# LPCB278_-_RELAYS.net
KiCad netlist of a schematic drawn in Altium Designer
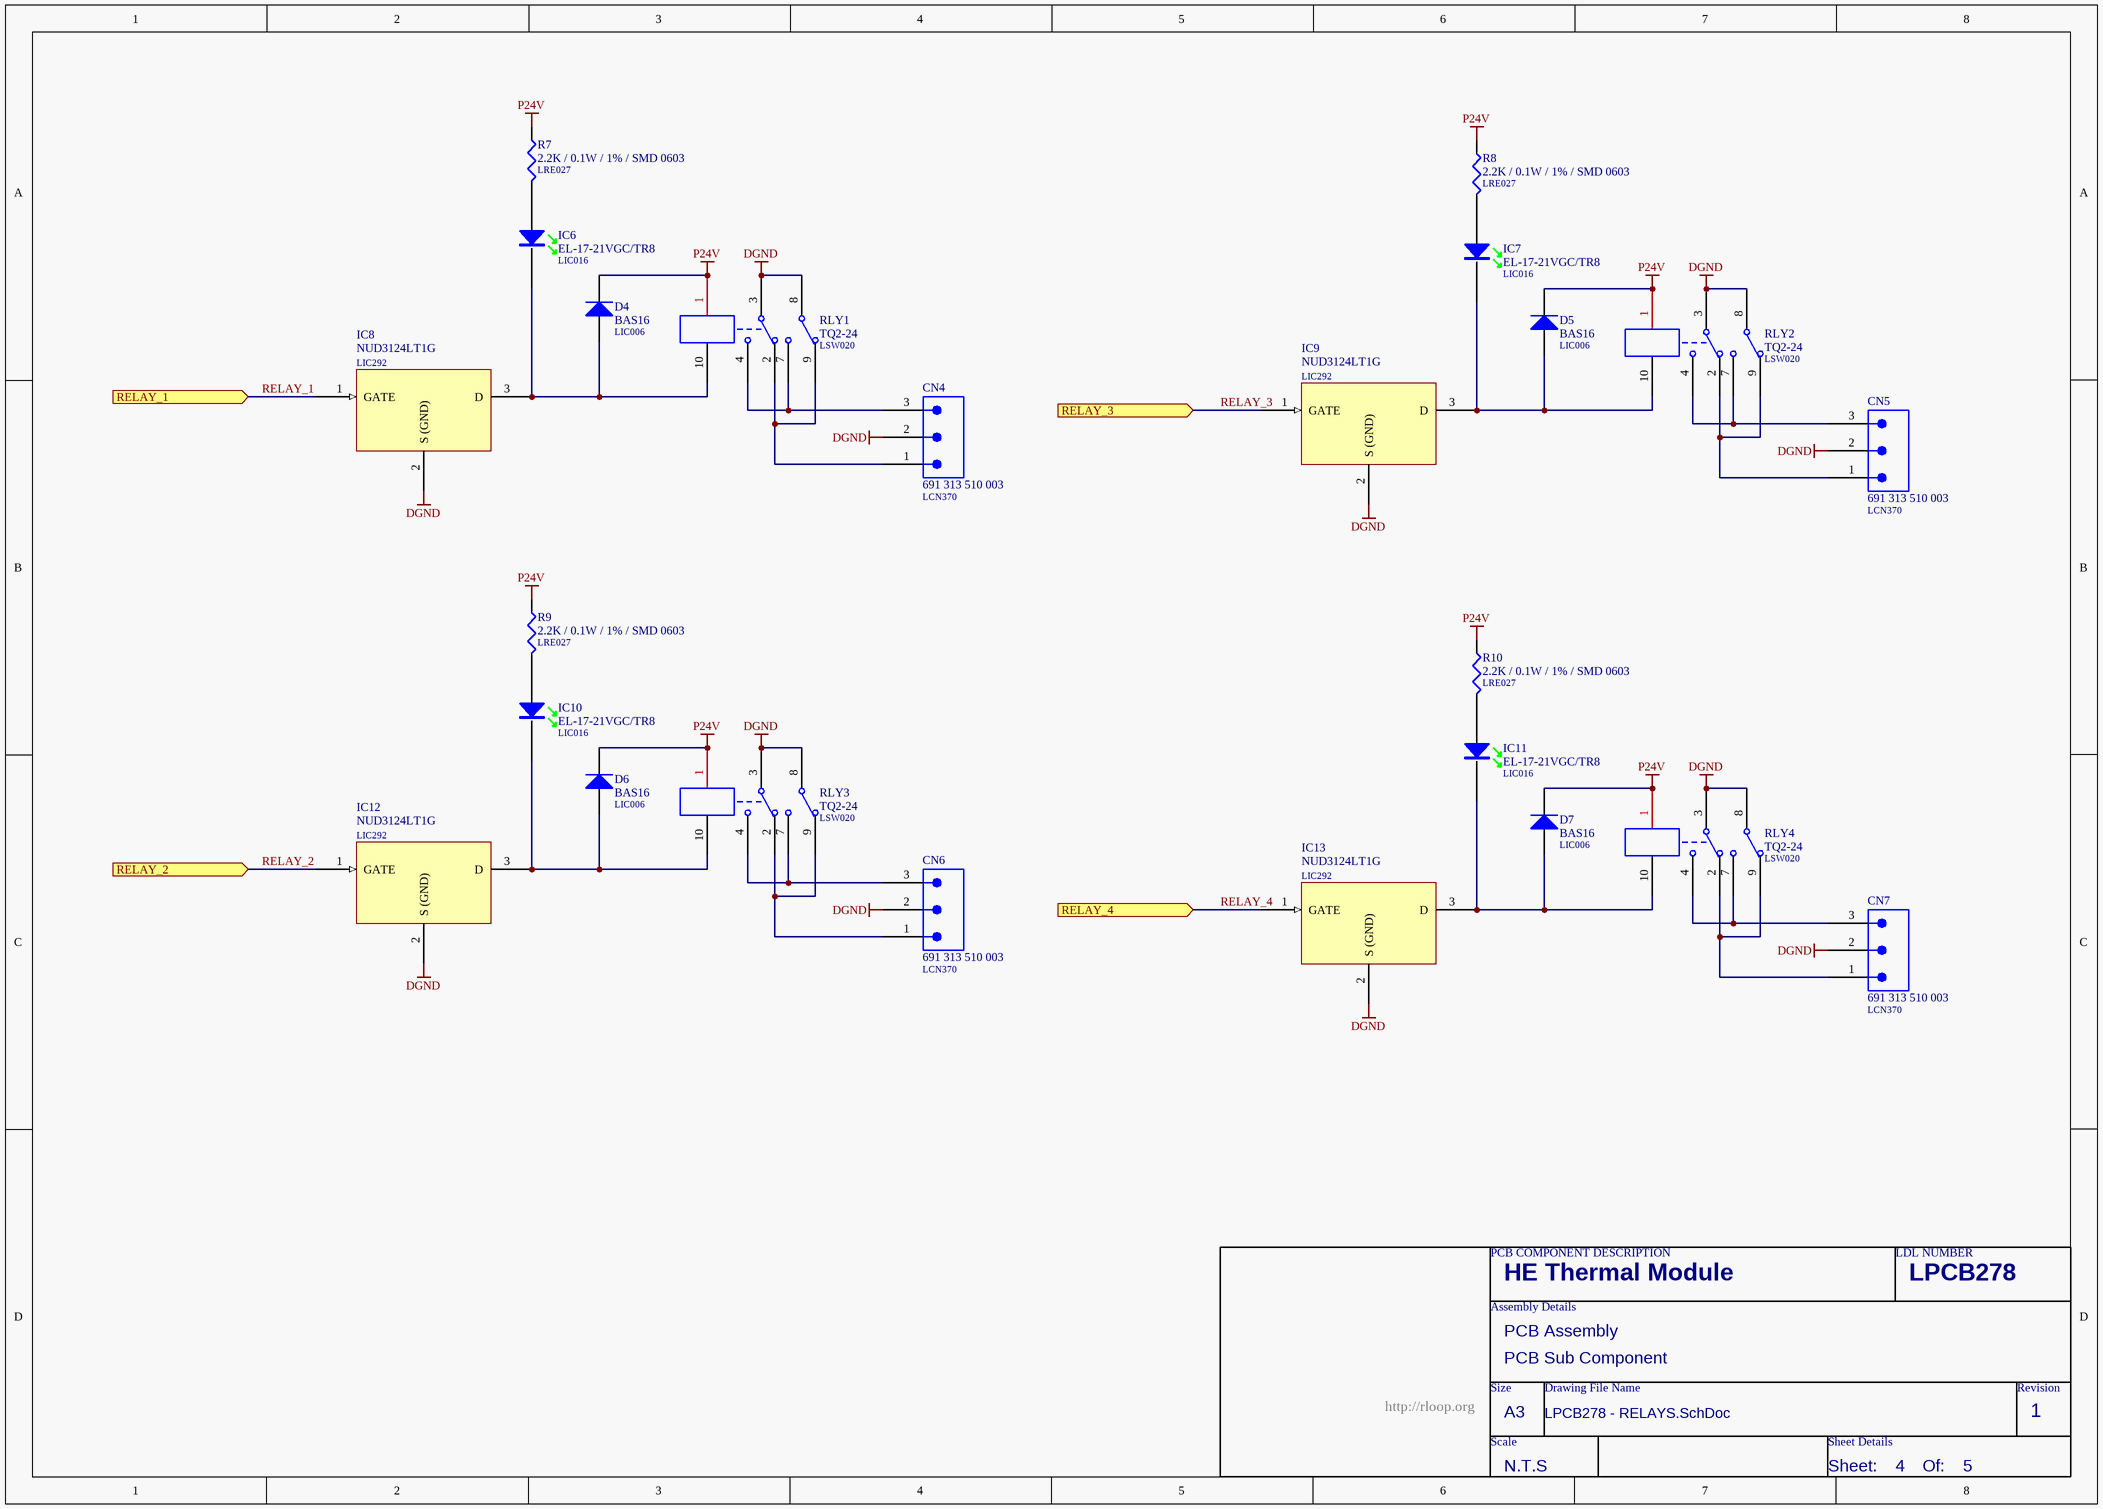
[diagram p0: LPCB278 - RELAYS.SchDoc]

(export (version "E")
  (design (tool "Eeschema 10.0.6"))
  (components
    (comp (ref "CN4")
      (value "691 313 510 003")
      (footprint "691 313 510 003")
      (description "Connector, Pluggable Terminal Block, 5.08mm, 3 Way, PTH")
      (fields (field (name "LDL_NUMBER") "LCN370"))
      (libsource (lib "LDL_Connectors") (part "691 313 510 003"))
    )
    (comp (ref "CN5")
      (value "691 313 510 003")
      (footprint "691 313 510 003")
      (description "Connector, Pluggable Terminal Block, 5.08mm, 3 Way, PTH")
      (fields (field (name "LDL_NUMBER") "LCN370"))
      (libsource (lib "LDL_Connectors") (part "691 313 510 003"))
    )
    (comp (ref "CN6")
      (value "691 313 510 003")
      (footprint "691 313 510 003")
      (description "Connector, Pluggable Terminal Block, 5.08mm, 3 Way, PTH")
      (fields (field (name "LDL_NUMBER") "LCN370"))
      (libsource (lib "LDL_Connectors") (part "691 313 510 003"))
    )
    (comp (ref "CN7")
      (value "691 313 510 003")
      (footprint "691 313 510 003")
      (description "Connector, Pluggable Terminal Block, 5.08mm, 3 Way, PTH")
      (fields (field (name "LDL_NUMBER") "LCN370"))
      (libsource (lib "LDL_Connectors") (part "691 313 510 003"))
    )
    (comp (ref "D4")
      (value "BAS16")
      (footprint "LFP021__SOT23")
      (description "Diode, Small Signal, 0.2A, 85V, SMD SOT-23 [LIC006]")
      (fields (field (name "LDL_NUMBER") "LIC006"))
      (libsource (lib "LDL_Semiconductors") (part "BAS16"))
    )
    (comp (ref "D5")
      (value "BAS16")
      (footprint "LFP021__SOT23")
      (description "Diode, Small Signal, 0.2A, 85V, SMD SOT-23 [LIC006]")
      (fields (field (name "LDL_NUMBER") "LIC006"))
      (libsource (lib "LDL_Semiconductors") (part "BAS16"))
    )
    (comp (ref "D6")
      (value "BAS16")
      (footprint "LFP021__SOT23")
      (description "Diode, Small Signal, 0.2A, 85V, SMD SOT-23 [LIC006]")
      (fields (field (name "LDL_NUMBER") "LIC006"))
      (libsource (lib "LDL_Semiconductors") (part "BAS16"))
    )
    (comp (ref "D7")
      (value "BAS16")
      (footprint "LFP021__SOT23")
      (description "Diode, Small Signal, 0.2A, 85V, SMD SOT-23 [LIC006]")
      (fields (field (name "LDL_NUMBER") "LIC006"))
      (libsource (lib "LDL_Semiconductors") (part "BAS16"))
    )
    (comp (ref "IC6")
      (value "EL-17-21VGC/TR8")
      (footprint "CR2012-0805-LED")
      (description "LED, SMD, 0805 Green [LIC016]")
      (fields (field (name "LDL_NUMBER") "LIC016"))
      (libsource (lib "LDL_Semiconductors") (part "EL-17-21VGC/TR8"))
    )
    (comp (ref "IC7")
      (value "EL-17-21VGC/TR8")
      (footprint "CR2012-0805-LED")
      (description "LED, SMD, 0805 Green [LIC016]")
      (fields (field (name "LDL_NUMBER") "LIC016"))
      (libsource (lib "LDL_Semiconductors") (part "EL-17-21VGC/TR8"))
    )
    (comp (ref "IC8")
      (value "NUD3124LT1G")
      (footprint "LFP021__SOT23")
      (description "IC, Relay Driver, 28V Industrial, SMD SOT23 [LIC292]")
      (fields (field (name "LDL_NUMBER") "LIC292"))
      (libsource (lib "LDL_Semiconductors") (part "NUD3124LT1G"))
    )
    (comp (ref "IC9")
      (value "NUD3124LT1G")
      (footprint "LFP021__SOT23")
      (description "IC, Relay Driver, 28V Industrial, SMD SOT23 [LIC292]")
      (fields (field (name "LDL_NUMBER") "LIC292"))
      (libsource (lib "LDL_Semiconductors") (part "NUD3124LT1G"))
    )
    (comp (ref "IC10")
      (value "EL-17-21VGC/TR8")
      (footprint "CR2012-0805-LED")
      (description "LED, SMD, 0805 Green [LIC016]")
      (fields (field (name "LDL_NUMBER") "LIC016"))
      (libsource (lib "LDL_Semiconductors") (part "EL-17-21VGC/TR8"))
    )
    (comp (ref "IC11")
      (value "EL-17-21VGC/TR8")
      (footprint "CR2012-0805-LED")
      (description "LED, SMD, 0805 Green [LIC016]")
      (fields (field (name "LDL_NUMBER") "LIC016"))
      (libsource (lib "LDL_Semiconductors") (part "EL-17-21VGC/TR8"))
    )
    (comp (ref "IC12")
      (value "NUD3124LT1G")
      (footprint "LFP021__SOT23")
      (description "IC, Relay Driver, 28V Industrial, SMD SOT23 [LIC292]")
      (fields (field (name "LDL_NUMBER") "LIC292"))
      (libsource (lib "LDL_Semiconductors") (part "NUD3124LT1G"))
    )
    (comp (ref "IC13")
      (value "NUD3124LT1G")
      (footprint "LFP021__SOT23")
      (description "IC, Relay Driver, 28V Industrial, SMD SOT23 [LIC292]")
      (fields (field (name "LDL_NUMBER") "LIC292"))
      (libsource (lib "LDL_Semiconductors") (part "NUD3124LT1G"))
    )
    (comp (ref "R7")
      (value "2.2K / 0.1W / 1% / SMD 0603")
      (footprint "LFP020__CR1608-0603-IPC7351_B")
      (description "Resistor, Ceramic Chip, 2.2K, 0.1W, 1%, SMD 0603 [LRE027]")
      (fields (field (name "LDL_NUMBER") "LRE027"))
      (libsource (lib "LDL_Resistors") (part "2.2K / 0.1W / 1% / SMD 0603"))
    )
    (comp (ref "R8")
      (value "2.2K / 0.1W / 1% / SMD 0603")
      (footprint "LFP020__CR1608-0603-IPC7351_B")
      (description "Resistor, Ceramic Chip, 2.2K, 0.1W, 1%, SMD 0603 [LRE027]")
      (fields (field (name "LDL_NUMBER") "LRE027"))
      (libsource (lib "LDL_Resistors") (part "2.2K / 0.1W / 1% / SMD 0603"))
    )
    (comp (ref "R9")
      (value "2.2K / 0.1W / 1% / SMD 0603")
      (footprint "LFP020__CR1608-0603-IPC7351_B")
      (description "Resistor, Ceramic Chip, 2.2K, 0.1W, 1%, SMD 0603 [LRE027]")
      (fields (field (name "LDL_NUMBER") "LRE027"))
      (libsource (lib "LDL_Resistors") (part "2.2K / 0.1W / 1% / SMD 0603"))
    )
    (comp (ref "R10")
      (value "2.2K / 0.1W / 1% / SMD 0603")
      (footprint "LFP020__CR1608-0603-IPC7351_B")
      (description "Resistor, Ceramic Chip, 2.2K, 0.1W, 1%, SMD 0603 [LRE027]")
      (fields (field (name "LDL_NUMBER") "LRE027"))
      (libsource (lib "LDL_Resistors") (part "2.2K / 0.1W / 1% / SMD 0603"))
    )
    (comp (ref "RLY1")
      (value "TQ2-24")
      (footprint "TQ2")
      (description "Relay, DPDT, Non Latching, 24VDC Coil, 1A Rating, PTH")
      (fields (field (name "LDL_NUMBER") "LSW020"))
      (libsource (lib "LDL_Switching") (part "TQ2-24"))
    )
    (comp (ref "RLY2")
      (value "TQ2-24")
      (footprint "TQ2")
      (description "Relay, DPDT, Non Latching, 24VDC Coil, 1A Rating, PTH")
      (fields (field (name "LDL_NUMBER") "LSW020"))
      (libsource (lib "LDL_Switching") (part "TQ2-24"))
    )
    (comp (ref "RLY3")
      (value "TQ2-24")
      (footprint "TQ2")
      (description "Relay, DPDT, Non Latching, 24VDC Coil, 1A Rating, PTH")
      (fields (field (name "LDL_NUMBER") "LSW020"))
      (libsource (lib "LDL_Switching") (part "TQ2-24"))
    )
    (comp (ref "RLY4")
      (value "TQ2-24")
      (footprint "TQ2")
      (description "Relay, DPDT, Non Latching, 24VDC Coil, 1A Rating, PTH")
      (fields (field (name "LDL_NUMBER") "LSW020"))
      (libsource (lib "LDL_Switching") (part "TQ2-24"))
    )
  )
  (nets
    (net (code "1") (name "/RELAY_1") (class "Default")
      (node (ref "IC8") (pin "1") (pinfunction "GATE_1") (pintype "input"))
    )
    (net (code "2") (name "/RELAY_2") (class "Default")
      (node (ref "IC12") (pin "1") (pinfunction "GATE_1") (pintype "input"))
    )
    (net (code "3") (name "/RELAY_3") (class "Default")
      (node (ref "IC9") (pin "1") (pinfunction "GATE_1") (pintype "input"))
    )
    (net (code "4") (name "/RELAY_4") (class "Default")
      (node (ref "IC13") (pin "1") (pinfunction "GATE_1") (pintype "input"))
    )
    (net (code "5") (name "DGND") (class "Default")
      (node (ref "CN4") (pin "2") (pinfunction "2_2") (pintype "passive"))
      (node (ref "CN5") (pin "2") (pinfunction "2_2") (pintype "passive"))
      (node (ref "CN6") (pin "2") (pinfunction "2_2") (pintype "passive"))
      (node (ref "CN7") (pin "2") (pinfunction "2_2") (pintype "passive"))
      (node (ref "IC12") (pin "2") (pinfunction "S_(GND)_2") (pintype "passive"))
      (node (ref "IC13") (pin "2") (pinfunction "S_(GND)_2") (pintype "passive"))
      (node (ref "IC8") (pin "2") (pinfunction "S_(GND)_2") (pintype "passive"))
      (node (ref "IC9") (pin "2") (pinfunction "S_(GND)_2") (pintype "passive"))
      (node (ref "RLY1") (pin "3") (pinfunction "3_3") (pintype "passive"))
      (node (ref "RLY1") (pin "8") (pinfunction "8_8") (pintype "passive"))
      (node (ref "RLY2") (pin "3") (pinfunction "3_3") (pintype "passive"))
      (node (ref "RLY2") (pin "8") (pinfunction "8_8") (pintype "passive"))
      (node (ref "RLY3") (pin "3") (pinfunction "3_3") (pintype "passive"))
      (node (ref "RLY3") (pin "8") (pinfunction "8_8") (pintype "passive"))
      (node (ref "RLY4") (pin "3") (pinfunction "3_3") (pintype "passive"))
      (node (ref "RLY4") (pin "8") (pinfunction "8_8") (pintype "passive"))
    )
    (net (code "6") (name "Net-(CN4-Pad1)") (class "Default")
      (node (ref "CN4") (pin "1") (pinfunction "1_1") (pintype "passive"))
      (node (ref "RLY1") (pin "2") (pinfunction "2_2") (pintype "passive"))
      (node (ref "RLY1") (pin "9") (pinfunction "9_9") (pintype "passive"))
    )
    (net (code "7") (name "Net-(CN4-Pad3)") (class "Default")
      (node (ref "CN4") (pin "3") (pinfunction "3_3") (pintype "passive"))
      (node (ref "RLY1") (pin "4") (pinfunction "4_4") (pintype "passive"))
      (node (ref "RLY1") (pin "7") (pinfunction "7_7") (pintype "passive"))
    )
    (net (code "8") (name "Net-(CN5-Pad1)") (class "Default")
      (node (ref "CN5") (pin "1") (pinfunction "1_1") (pintype "passive"))
      (node (ref "RLY2") (pin "2") (pinfunction "2_2") (pintype "passive"))
      (node (ref "RLY2") (pin "9") (pinfunction "9_9") (pintype "passive"))
    )
    (net (code "9") (name "Net-(CN5-Pad3)") (class "Default")
      (node (ref "CN5") (pin "3") (pinfunction "3_3") (pintype "passive"))
      (node (ref "RLY2") (pin "4") (pinfunction "4_4") (pintype "passive"))
      (node (ref "RLY2") (pin "7") (pinfunction "7_7") (pintype "passive"))
    )
    (net (code "10") (name "Net-(CN6-Pad1)") (class "Default")
      (node (ref "CN6") (pin "1") (pinfunction "1_1") (pintype "passive"))
      (node (ref "RLY3") (pin "2") (pinfunction "2_2") (pintype "passive"))
      (node (ref "RLY3") (pin "9") (pinfunction "9_9") (pintype "passive"))
    )
    (net (code "11") (name "Net-(CN6-Pad3)") (class "Default")
      (node (ref "CN6") (pin "3") (pinfunction "3_3") (pintype "passive"))
      (node (ref "RLY3") (pin "4") (pinfunction "4_4") (pintype "passive"))
      (node (ref "RLY3") (pin "7") (pinfunction "7_7") (pintype "passive"))
    )
    (net (code "12") (name "Net-(CN7-Pad1)") (class "Default")
      (node (ref "CN7") (pin "1") (pinfunction "1_1") (pintype "passive"))
      (node (ref "RLY4") (pin "2") (pinfunction "2_2") (pintype "passive"))
      (node (ref "RLY4") (pin "9") (pinfunction "9_9") (pintype "passive"))
    )
    (net (code "13") (name "Net-(CN7-Pad3)") (class "Default")
      (node (ref "CN7") (pin "3") (pinfunction "3_3") (pintype "passive"))
      (node (ref "RLY4") (pin "4") (pinfunction "4_4") (pintype "passive"))
      (node (ref "RLY4") (pin "7") (pinfunction "7_7") (pintype "passive"))
    )
    (net (code "14") (name "Net-(D4-A)") (class "Default")
      (node (ref "D4") (pin "1") (pinfunction "A_1") (pintype "passive"))
      (node (ref "IC6") (pin "K") (pintype "passive"))
      (node (ref "IC8") (pin "3") (pinfunction "D_3") (pintype "passive"))
      (node (ref "RLY1") (pin "10") (pinfunction "10_10") (pintype "passive"))
    )
    (net (code "15") (name "Net-(D5-A)") (class "Default")
      (node (ref "D5") (pin "1") (pinfunction "A_1") (pintype "passive"))
      (node (ref "IC7") (pin "K") (pintype "passive"))
      (node (ref "IC9") (pin "3") (pinfunction "D_3") (pintype "passive"))
      (node (ref "RLY2") (pin "10") (pinfunction "10_10") (pintype "passive"))
    )
    (net (code "16") (name "Net-(D6-A)") (class "Default")
      (node (ref "D6") (pin "1") (pinfunction "A_1") (pintype "passive"))
      (node (ref "IC10") (pin "K") (pintype "passive"))
      (node (ref "IC12") (pin "3") (pinfunction "D_3") (pintype "passive"))
      (node (ref "RLY3") (pin "10") (pinfunction "10_10") (pintype "passive"))
    )
    (net (code "17") (name "Net-(D7-A)") (class "Default")
      (node (ref "D7") (pin "1") (pinfunction "A_1") (pintype "passive"))
      (node (ref "IC11") (pin "K") (pintype "passive"))
      (node (ref "IC13") (pin "3") (pinfunction "D_3") (pintype "passive"))
      (node (ref "RLY4") (pin "10") (pinfunction "10_10") (pintype "passive"))
    )
    (net (code "18") (name "Net-(IC6-PadA)") (class "Default")
      (node (ref "IC6") (pin "A") (pintype "passive"))
      (node (ref "R7") (pin "2") (pintype "passive"))
    )
    (net (code "19") (name "Net-(IC7-PadA)") (class "Default")
      (node (ref "IC7") (pin "A") (pintype "passive"))
      (node (ref "R8") (pin "2") (pintype "passive"))
    )
    (net (code "20") (name "Net-(IC10-PadA)") (class "Default")
      (node (ref "IC10") (pin "A") (pintype "passive"))
      (node (ref "R9") (pin "2") (pintype "passive"))
    )
    (net (code "21") (name "Net-(IC11-PadA)") (class "Default")
      (node (ref "IC11") (pin "A") (pintype "passive"))
      (node (ref "R10") (pin "2") (pintype "passive"))
    )
    (net (code "22") (name "P24V") (class "Default")
      (node (ref "D4") (pin "3") (pinfunction "K_3") (pintype "passive"))
      (node (ref "D5") (pin "3") (pinfunction "K_3") (pintype "passive"))
      (node (ref "D6") (pin "3") (pinfunction "K_3") (pintype "passive"))
      (node (ref "D7") (pin "3") (pinfunction "K_3") (pintype "passive"))
      (node (ref "R10") (pin "1") (pintype "passive"))
      (node (ref "R7") (pin "1") (pintype "passive"))
      (node (ref "R8") (pin "1") (pintype "passive"))
      (node (ref "R9") (pin "1") (pintype "passive"))
      (node (ref "RLY1") (pin "1") (pinfunction "1_1") (pintype "passive"))
      (node (ref "RLY2") (pin "1") (pinfunction "1_1") (pintype "passive"))
      (node (ref "RLY3") (pin "1") (pinfunction "1_1") (pintype "passive"))
      (node (ref "RLY4") (pin "1") (pinfunction "1_1") (pintype "passive"))
    )
  )
)
